# 5v_Inputs.net
KiCad netlist of a schematic drawn in Altium Designer
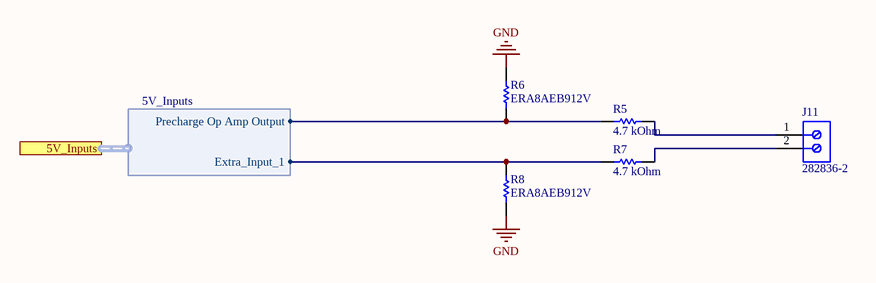
[diagram p0: 5v_Inputs.SchDoc]

(export (version "E")
  (design (tool "Eeschema 10.0.6"))
  (components
    (comp (ref "J11")
      (value "282836-2")
      (footprint "TECO-282836-2_V")
      (description "Female Header, Pitch 5 mm, 1 x 2 Position, Height 10 mm, Tail Length 3.5 mm, Rohs, Bulk")
      (fields (field (name "VOLTAGE") "300V") (field (name "MANUFACTURER") "TE Connectivity"))
      (libsource (lib "Altium Content Vault") (part "CN-1P-F-TB2"))
    )
    (comp (ref "R5")
      (value "4.7 kOhm")
      (footprint "RESC3216X60X45ML15T20")
      (description "Chip Resistor, 4.7 KOhm, +/- 1%, 0.25 W, -55 to 155 degC, 1206 (3216 Metric), RoHS, Tape and Reel")
      (fields (field (name "MANUFACTURER") "Vishay Semiconductor") (field (name "TOLERANCE") "1%"))
      (libsource (lib "Altium Content Vault") (part "RES-2"))
    )
    (comp (ref "R6")
      (value "ERA8AEB912V")
      (footprint "RESC3216X70X50ML20T25")
      (fields (field (name "MANUFACTURER") "Panasonic"))
      (libsource (lib "Altium Content Vault") (part "RES"))
    )
    (comp (ref "R7")
      (value "4.7 kOhm")
      (footprint "RESC3216X60X45ML15T20")
      (description "Chip Resistor, 4.7 KOhm, +/- 1%, 0.25 W, -55 to 155 degC, 1206 (3216 Metric), RoHS, Tape and Reel")
      (fields (field (name "MANUFACTURER") "Vishay Semiconductor") (field (name "TOLERANCE") "1%"))
      (libsource (lib "Altium Content Vault") (part "RES-2"))
    )
    (comp (ref "R8")
      (value "ERA8AEB912V")
      (footprint "RESC3216X70X50ML20T25")
      (fields (field (name "MANUFACTURER") "Panasonic"))
      (libsource (lib "Altium Content Vault") (part "RES"))
    )
  )
  (nets
    (net (code "3") (name "GND") (class "Default")
      (node (ref "R6") (pin "1") (pinfunction "1_1") (pintype "passive"))
      (node (ref "R8") (pin "2") (pinfunction "2_2") (pintype "passive"))
    )
    (net (code "4") (name "Net-(J11-Pad1)") (class "Default")
      (node (ref "J11") (pin "1") (pinfunction "1_1") (pintype "passive"))
      (node (ref "R5") (pin "1") (pinfunction "1_1") (pintype "passive"))
    )
    (net (code "5") (name "Net-(J11-Pad2)") (class "Default")
      (node (ref "J11") (pin "2") (pinfunction "2_2") (pintype "passive"))
      (node (ref "R7") (pin "1") (pinfunction "1_1") (pintype "passive"))
    )
    (net (code "6") (name "Net-(R5-Pad2)") (class "Default")
      (node (ref "R5") (pin "2") (pinfunction "2_2") (pintype "passive"))
      (node (ref "R6") (pin "2") (pinfunction "2_2") (pintype "passive"))
    )
    (net (code "7") (name "Net-(R7-Pad2)") (class "Default")
      (node (ref "R7") (pin "2") (pinfunction "2_2") (pintype "passive"))
      (node (ref "R8") (pin "1") (pinfunction "1_1") (pintype "passive"))
    )
  )
)
